# P02_BCS1_JTAG_Clock_LED.net
KiCad netlist of a schematic drawn in Altium Designer
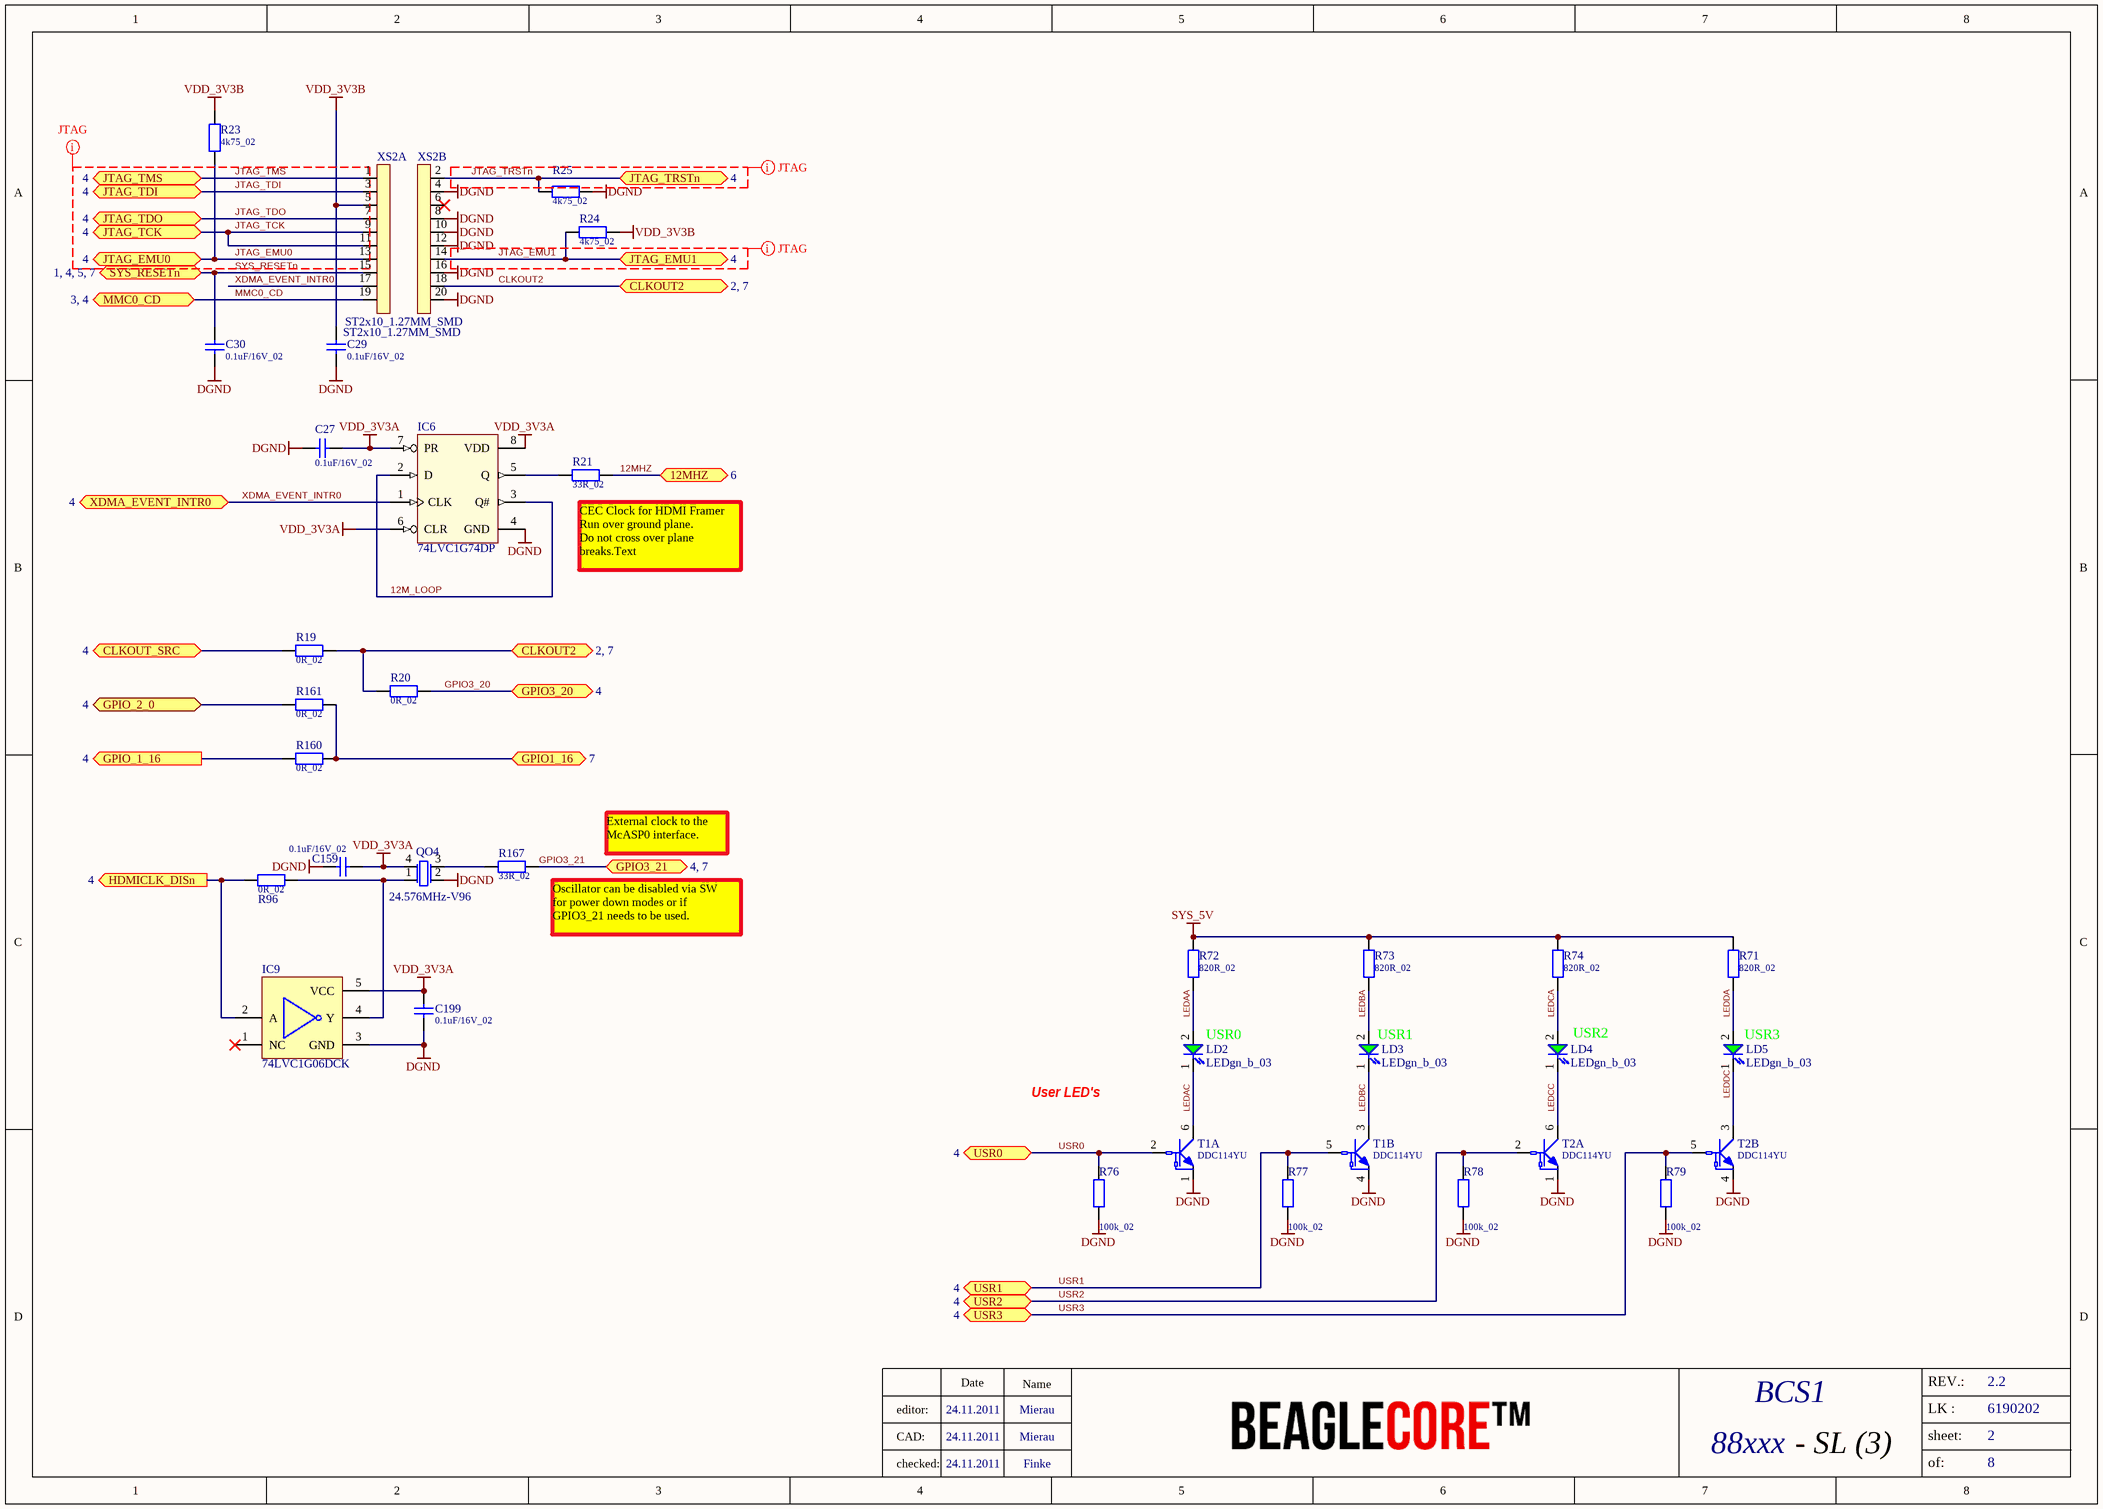
[diagram p0: P02_BCS1_JTAG, Clock, LED.SchDoc]

(export (version "E")
  (design (tool "Eeschema 10.0.6"))
  (components
    (comp (ref "C27")
      (value "0.1uF/16V_02")
      (footprint "CC1005-0402")
      (description "Capacitor 0402 16V Y5V")
      (libsource (lib "*") (part "C0.1uF/16V_02"))
    )
    (comp (ref "C29")
      (value "0.1uF/16V_02")
      (footprint "CC1005-0402")
      (description "Capacitor 0402 16V Y5V")
      (libsource (lib "*") (part "C0.1uF/16V_02"))
    )
    (comp (ref "C30")
      (value "0.1uF/16V_02")
      (footprint "CC1005-0402")
      (description "Capacitor 0402 16V Y5V")
      (libsource (lib "*") (part "C0.1uF/16V_02"))
    )
    (comp (ref "C159")
      (value "0.1uF/16V_02")
      (footprint "CC1005-0402")
      (description "Capacitor 0402 16V Y5V")
      (libsource (lib "*") (part "C0.1uF/16V_02"))
    )
    (comp (ref "C199")
      (value "0.1uF/16V_02")
      (footprint "CC1005-0402")
      (description "Capacitor 0402 16V Y5V")
      (libsource (lib "*") (part "C0.1uF/16V_02"))
    )
    (comp (ref "IC6")
      (value "74LVC1G74DP")
      (footprint "TSSOP8 - 3x3")
      (description "Dual D-Type Positive-Edge-Triggered Flip-Flop with Set and Reset")
      (libsource (lib "*") (part "IC74LVC1G74DP"))
    )
    (comp (ref "IC9")
      (value "74LVC1G06DCK")
      (footprint "SOT353")
      (description "Single Inverter Buffer/Driver With Open-Drain Output")
      (libsource (lib "*") (part "IC74LVC1G06DCK"))
    )
    (comp (ref "LD2")
      (value "LEDgn_b_03")
      (footprint "CD1608-0603")
      (description "Leuchtdiode bright grün 0603, RV(5mA)@3V3= 100OHM")
      (libsource (lib "*") (part "LD_LEDgn_bright_03"))
    )
    (comp (ref "LD3")
      (value "LEDgn_b_03")
      (footprint "CD1608-0603")
      (description "Leuchtdiode bright grün 0603, RV(5mA)@3V3= 100OHM")
      (libsource (lib "*") (part "LD_LEDgn_bright_03"))
    )
    (comp (ref "LD4")
      (value "LEDgn_b_03")
      (footprint "CD1608-0603")
      (description "Leuchtdiode bright grün 0603, RV(5mA)@3V3= 100OHM")
      (libsource (lib "*") (part "LD_LEDgn_bright_03"))
    )
    (comp (ref "LD5")
      (value "LEDgn_b_03")
      (footprint "CD1608-0603")
      (description "Leuchtdiode bright grün 0603, RV(5mA)@3V3= 100OHM")
      (libsource (lib "*") (part "LD_LEDgn_bright_03"))
    )
    (comp (ref "QO4")
      (value "24.576MHz-V96")
      (footprint "QUARZ KXO-V96")
      (description "Quarz Oszillator 24.576MHz; KXO-V96")
      (libsource (lib "*") (part "QO24.576MHz_V96"))
    )
    (comp (ref "R19")
      (value "0R_02")
      (footprint "CR1005-0402")
      (description "Resistor 0402")
      (libsource (lib "*") (part "R0R_02"))
    )
    (comp (ref "R20")
      (value "0R_02")
      (footprint "CR1005-0402")
      (description "Resistor 0402")
      (libsource (lib "*") (part "R0R_02"))
    )
    (comp (ref "R21")
      (value "33R_02")
      (footprint "CR1005-0402")
      (description "Resistor 0402")
      (libsource (lib "*") (part "R33R_02"))
    )
    (comp (ref "R23")
      (value "4k75_02")
      (footprint "CR1005-0402")
      (description "Resistor 0402")
      (libsource (lib "") (part "R4k75_02_2"))
    )
    (comp (ref "R24")
      (value "4k75_02")
      (footprint "CR1005-0402")
      (description "Resistor 0402")
      (libsource (lib "") (part "R4k75_02_1"))
    )
    (comp (ref "R25")
      (value "4k75_02")
      (footprint "CR1005-0402")
      (description "Resistor 0402")
      (libsource (lib "*") (part "R4k75_02"))
    )
    (comp (ref "R71")
      (value "820R_02")
      (footprint "CR1005-0402")
      (description "Resistor 0402")
      (libsource (lib "*") (part "R820R_02"))
    )
    (comp (ref "R72")
      (value "820R_02")
      (footprint "CR1005-0402")
      (description "Resistor 0402")
      (libsource (lib "*") (part "R820R_02"))
    )
    (comp (ref "R73")
      (value "820R_02")
      (footprint "CR1005-0402")
      (description "Resistor 0402")
      (libsource (lib "*") (part "R820R_02"))
    )
    (comp (ref "R74")
      (value "820R_02")
      (footprint "CR1005-0402")
      (description "Resistor 0402")
      (libsource (lib "*") (part "R820R_02"))
    )
    (comp (ref "R76")
      (value "100k_02")
      (footprint "CR1005-0402")
      (description "Resistor 0402")
      (libsource (lib "*") (part "R100k_02"))
    )
    (comp (ref "R77")
      (value "100k_02")
      (footprint "CR1005-0402")
      (description "Resistor 0402")
      (libsource (lib "*") (part "R100k_02"))
    )
    (comp (ref "R78")
      (value "100k_02")
      (footprint "CR1005-0402")
      (description "Resistor 0402")
      (libsource (lib "*") (part "R100k_02"))
    )
    (comp (ref "R79")
      (value "100k_02")
      (footprint "CR1005-0402")
      (description "Resistor 0402")
      (libsource (lib "*") (part "R100k_02"))
    )
    (comp (ref "R96")
      (value "0R_02")
      (footprint "CR1005-0402")
      (description "Resistor 0402")
      (libsource (lib "*") (part "R0R_02"))
    )
    (comp (ref "R160")
      (value "0R_02")
      (footprint "CR1005-0402")
      (description "Resistor 0402")
      (libsource (lib "*") (part "R0R_02"))
    )
    (comp (ref "R161")
      (value "0R_02")
      (footprint "CR1005-0402")
      (description "Resistor 0402")
      (libsource (lib "*") (part "R0R_02"))
    )
    (comp (ref "R167")
      (value "33R_02")
      (footprint "CR1005-0402")
      (description "Resistor 0402")
      (libsource (lib "*") (part "R33R_02"))
    )
    (comp (ref "T1")
      (value "DDC114YU")
      (footprint "SOT363")
      (description "2 fach NPN m Widerständen Vceo=40V, Ic=0.1A")
      (libsource (lib "*") (part "TDDC114YU"))
    )
    (comp (ref "T2")
      (value "DDC114YU")
      (footprint "SOT363")
      (description "2 fach NPN m Widerständen Vceo=40V, Ic=0.1A")
      (libsource (lib "*") (part "TDDC114YU"))
    )
    (comp (ref "XS2")
      (value "ST2x10_1.27MM_SMD")
      (footprint "ST2X10SMD-1.27_SAMTEC")
      (description "Stiftleiste 20polig, 1.27mm pitch, Samtec")
      (libsource (lib "") (part "XST2X10_1.27MM_SMD_SAM_1"))
    )
  )
  (nets
    (net (code "1") (name "/12MHZ") (class "Default")
      (node (ref "R21") (pin "2") (pinfunction "2_2") (pintype "passive"))
    )
    (net (code "2") (name "/12M_LOOP") (class "Default")
      (node (ref "IC6") (pin "2") (pinfunction "D_2") (pintype "input"))
      (node (ref "IC6") (pin "3") (pinfunction "Q#_3") (pintype "output"))
    )
    (net (code "3") (name "/CLKOUT2") (class "Default")
      (node (ref "R19") (pin "2") (pinfunction "2_2") (pintype "passive"))
      (node (ref "R20") (pin "1") (pinfunction "1_1") (pintype "passive"))
      (node (ref "XS2") (pin "18") (pinfunction "18_18") (pintype "passive"))
    )
    (net (code "4") (name "/CLKOUT_SRC") (class "Default")
      (node (ref "R19") (pin "1") (pinfunction "1_1") (pintype "passive"))
    )
    (net (code "5") (name "/GPIO1_16") (class "Default")
      (node (ref "R160") (pin "2") (pinfunction "2_2") (pintype "passive"))
      (node (ref "R161") (pin "2") (pinfunction "2_2") (pintype "passive"))
    )
    (net (code "6") (name "/GPIO3_20") (class "Default")
      (node (ref "R20") (pin "2") (pinfunction "2_2") (pintype "passive"))
    )
    (net (code "7") (name "/GPIO3_21") (class "Default")
      (node (ref "R167") (pin "2") (pinfunction "2_2") (pintype "passive"))
    )
    (net (code "8") (name "/GPIO_1_16") (class "Default")
      (node (ref "R160") (pin "1") (pinfunction "1_1") (pintype "passive"))
    )
    (net (code "9") (name "/GPIO_2_0") (class "Default")
      (node (ref "R161") (pin "1") (pinfunction "1_1") (pintype "passive"))
    )
    (net (code "10") (name "/HDMICLK_DISn") (class "Default")
      (node (ref "IC9") (pin "2") (pinfunction "A_2") (pintype "passive"))
      (node (ref "R96") (pin "1") (pinfunction "1_1") (pintype "passive"))
    )
    (net (code "11") (name "/JTAG_EMU0") (class "Default")
      (node (ref "R23") (pin "2") (pinfunction "2_2") (pintype "passive"))
      (node (ref "XS2") (pin "13") (pinfunction "13_13") (pintype "passive"))
    )
    (net (code "12") (name "/JTAG_EMU1") (class "Default")
      (node (ref "R24") (pin "2") (pinfunction "2_2") (pintype "passive"))
      (node (ref "XS2") (pin "14") (pinfunction "14_14") (pintype "passive"))
    )
    (net (code "13") (name "/JTAG_TCK") (class "Default")
      (node (ref "XS2") (pin "11") (pinfunction "11_11") (pintype "passive"))
      (node (ref "XS2") (pin "9") (pinfunction "9_9") (pintype "passive"))
    )
    (net (code "14") (name "/JTAG_TDI") (class "Default")
      (node (ref "XS2") (pin "3") (pinfunction "3_3") (pintype "passive"))
    )
    (net (code "15") (name "/JTAG_TDO") (class "Default")
      (node (ref "XS2") (pin "7") (pinfunction "7_7") (pintype "passive"))
    )
    (net (code "16") (name "/JTAG_TMS") (class "Default")
      (node (ref "XS2") (pin "1") (pinfunction "1_1") (pintype "passive"))
    )
    (net (code "17") (name "/JTAG_TRSTn") (class "Default")
      (node (ref "R25") (pin "1") (pinfunction "1_1") (pintype "passive"))
      (node (ref "XS2") (pin "2") (pinfunction "2_2") (pintype "passive"))
    )
    (net (code "18") (name "/LEDAA") (class "Default")
      (node (ref "LD2") (pin "2") (pinfunction "A_2") (pintype "passive"))
      (node (ref "R72") (pin "2") (pinfunction "2_2") (pintype "passive"))
    )
    (net (code "19") (name "/LEDAC") (class "Default")
      (node (ref "LD2") (pin "1") (pinfunction "K_1") (pintype "passive"))
      (node (ref "T1") (pin "6") (pinfunction "COLLECTOR1_6") (pintype "passive"))
    )
    (net (code "20") (name "/LEDBA") (class "Default")
      (node (ref "LD3") (pin "2") (pinfunction "A_2") (pintype "passive"))
      (node (ref "R73") (pin "2") (pinfunction "2_2") (pintype "passive"))
    )
    (net (code "21") (name "/LEDBC") (class "Default")
      (node (ref "LD3") (pin "1") (pinfunction "K_1") (pintype "passive"))
      (node (ref "T1") (pin "3") (pinfunction "COLLECTOR2_3") (pintype "passive"))
    )
    (net (code "22") (name "/LEDCA") (class "Default")
      (node (ref "LD4") (pin "2") (pinfunction "A_2") (pintype "passive"))
      (node (ref "R74") (pin "2") (pinfunction "2_2") (pintype "passive"))
    )
    (net (code "23") (name "/LEDCC") (class "Default")
      (node (ref "LD4") (pin "1") (pinfunction "K_1") (pintype "passive"))
      (node (ref "T2") (pin "6") (pinfunction "COLLECTOR1_6") (pintype "passive"))
    )
    (net (code "24") (name "/LEDDA") (class "Default")
      (node (ref "LD5") (pin "2") (pinfunction "A_2") (pintype "passive"))
      (node (ref "R71") (pin "2") (pinfunction "2_2") (pintype "passive"))
    )
    (net (code "25") (name "/LEDDC") (class "Default")
      (node (ref "LD5") (pin "1") (pinfunction "K_1") (pintype "passive"))
      (node (ref "T2") (pin "3") (pinfunction "COLLECTOR2_3") (pintype "passive"))
    )
    (net (code "26") (name "/MMC0_CD") (class "Default")
      (node (ref "XS2") (pin "19") (pinfunction "19_19") (pintype "passive"))
    )
    (net (code "27") (name "/SYS_RESETn") (class "Default")
      (node (ref "C30") (pin "2") (pinfunction "2_2") (pintype "passive"))
      (node (ref "XS2") (pin "15") (pinfunction "15_15") (pintype "passive"))
    )
    (net (code "28") (name "/USR0") (class "Default")
      (node (ref "R76") (pin "2") (pinfunction "2_2") (pintype "passive"))
      (node (ref "T1") (pin "2") (pinfunction "BASE1_2") (pintype "passive"))
    )
    (net (code "29") (name "/USR1") (class "Default")
      (node (ref "R77") (pin "2") (pinfunction "2_2") (pintype "passive"))
      (node (ref "T1") (pin "5") (pinfunction "BASE2_5") (pintype "passive"))
    )
    (net (code "30") (name "/USR2") (class "Default")
      (node (ref "R78") (pin "2") (pinfunction "2_2") (pintype "passive"))
      (node (ref "T2") (pin "2") (pinfunction "BASE1_2") (pintype "passive"))
    )
    (net (code "31") (name "/USR3") (class "Default")
      (node (ref "R79") (pin "2") (pinfunction "2_2") (pintype "passive"))
      (node (ref "T2") (pin "5") (pinfunction "BASE2_5") (pintype "passive"))
    )
    (net (code "32") (name "/XDMA_EVENT_INTR0") (class "Default")
      (node (ref "IC6") (pin "1") (pinfunction "CLK_1") (pintype "input"))
      (node (ref "XS2") (pin "17") (pinfunction "17_17") (pintype "passive"))
    )
    (net (code "33") (name "DGND") (class "Default")
      (node (ref "C159") (pin "1") (pinfunction "1_1") (pintype "passive"))
      (node (ref "C199") (pin "1") (pinfunction "1_1") (pintype "passive"))
      (node (ref "C27") (pin "2") (pinfunction "2_2") (pintype "passive"))
      (node (ref "C29") (pin "1") (pinfunction "1_1") (pintype "passive"))
      (node (ref "C30") (pin "1") (pinfunction "1_1") (pintype "passive"))
      (node (ref "IC6") (pin "4") (pinfunction "GND_4") (pintype "passive"))
      (node (ref "IC9") (pin "3") (pinfunction "GND_3") (pintype "passive"))
      (node (ref "QO4") (pin "2") (pinfunction "GND_2") (pintype "passive"))
      (node (ref "R25") (pin "2") (pinfunction "2_2") (pintype "passive"))
      (node (ref "R76") (pin "1") (pinfunction "1_1") (pintype "passive"))
      (node (ref "R77") (pin "1") (pinfunction "1_1") (pintype "passive"))
      (node (ref "R78") (pin "1") (pinfunction "1_1") (pintype "passive"))
      (node (ref "R79") (pin "1") (pinfunction "1_1") (pintype "passive"))
      (node (ref "T1") (pin "1") (pinfunction "EMITTER1_1") (pintype "passive"))
      (node (ref "T1") (pin "4") (pinfunction "EMITTER2_4") (pintype "passive"))
      (node (ref "T2") (pin "1") (pinfunction "EMITTER1_1") (pintype "passive"))
      (node (ref "T2") (pin "4") (pinfunction "EMITTER2_4") (pintype "passive"))
      (node (ref "XS2") (pin "10") (pinfunction "10_10") (pintype "passive"))
      (node (ref "XS2") (pin "12") (pinfunction "12_12") (pintype "passive"))
      (node (ref "XS2") (pin "16") (pinfunction "16_16") (pintype "passive"))
      (node (ref "XS2") (pin "20") (pinfunction "20_20") (pintype "passive"))
      (node (ref "XS2") (pin "4") (pinfunction "4_4") (pintype "passive"))
      (node (ref "XS2") (pin "8") (pinfunction "8_8") (pintype "passive"))
    )
    (net (code "34") (name "Net-(IC6-Q)") (class "Default")
      (node (ref "IC6") (pin "5") (pinfunction "Q_5") (pintype "output"))
      (node (ref "R21") (pin "1") (pinfunction "1_1") (pintype "passive"))
    )
    (net (code "35") (name "Net-(IC9-Y)") (class "Default")
      (node (ref "IC9") (pin "4") (pinfunction "Y_4") (pintype "passive"))
      (node (ref "QO4") (pin "1") (pinfunction "EN#_1") (pintype "passive"))
      (node (ref "R96") (pin "2") (pinfunction "2_2") (pintype "passive"))
    )
    (net (code "36") (name "Net-(QO4-OUTPUT)") (class "Default")
      (node (ref "QO4") (pin "3") (pinfunction "OUTPUT_3") (pintype "passive"))
      (node (ref "R167") (pin "1") (pinfunction "1_1") (pintype "passive"))
    )
    (net (code "37") (name "SYS_5V") (class "Default")
      (node (ref "R71") (pin "1") (pinfunction "1_1") (pintype "passive"))
      (node (ref "R72") (pin "1") (pinfunction "1_1") (pintype "passive"))
      (node (ref "R73") (pin "1") (pinfunction "1_1") (pintype "passive"))
      (node (ref "R74") (pin "1") (pinfunction "1_1") (pintype "passive"))
    )
    (net (code "38") (name "VDD_3V3A") (class "Default")
      (node (ref "C159") (pin "2") (pinfunction "2_2") (pintype "passive"))
      (node (ref "C199") (pin "2") (pinfunction "2_2") (pintype "passive"))
      (node (ref "C27") (pin "1") (pinfunction "1_1") (pintype "passive"))
      (node (ref "IC6") (pin "6") (pinfunction "CLR_6") (pintype "input"))
      (node (ref "IC6") (pin "7") (pinfunction "PR_7") (pintype "input"))
      (node (ref "IC6") (pin "8") (pinfunction "VDD_8") (pintype "passive"))
      (node (ref "IC9") (pin "5") (pinfunction "VCC_5") (pintype "passive"))
      (node (ref "QO4") (pin "4") (pinfunction "VDD_4") (pintype "passive"))
    )
    (net (code "39") (name "VDD_3V3B") (class "Default")
      (node (ref "C29") (pin "2") (pinfunction "2_2") (pintype "passive"))
      (node (ref "R23") (pin "1") (pinfunction "1_1") (pintype "passive"))
      (node (ref "R24") (pin "1") (pinfunction "1_1") (pintype "passive"))
      (node (ref "XS2") (pin "5") (pinfunction "5_5") (pintype "passive"))
    )
    (net (code "40") (name "unconnected-(IC9-NC-Pad1)") (class "Default")
      (node (ref "IC9") (pin "1") (pinfunction "NC_1") (pintype "passive+no_connect"))
    )
    (net (code "41") (name "unconnected-(XS2-Pad6)") (class "Default")
      (node (ref "XS2") (pin "6") (pinfunction "6_6") (pintype "passive+no_connect"))
    )
  )
)
